# Mixers.net
KiCad netlist of a schematic drawn in Altium Designer
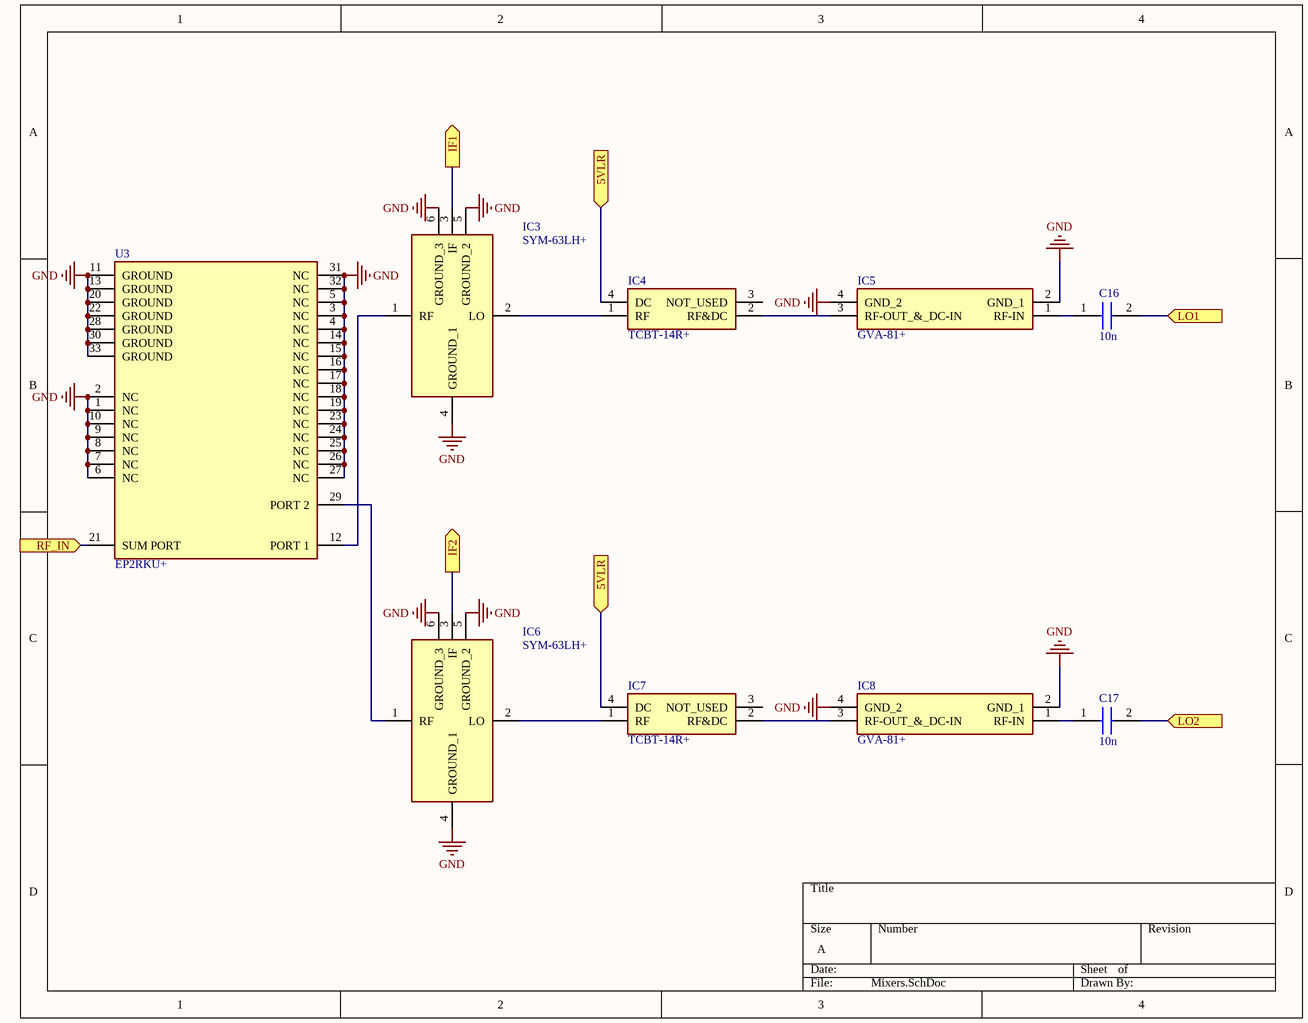
[diagram p0: Mixers.SchDoc]

(export (version "E")
  (design (tool "Eeschema 10.0.6"))
  (components
    (comp (ref "C16")
      (value "10n")
      (footprint "SamacSys:CAPC1005X61N")
      (description "Capacitor")
      (fields
        (field (name "MANUFACTURER_PART_NUMBER") "520L103KT16T")
        (field (name "MOUSER PART NUMBER") "581-520L103KT16T")
      )
      (libsource (lib "*") (part "520L103KT16T"))
    )
    (comp (ref "C17")
      (value "10n")
      (footprint "SamacSys:CAPC1005X61N")
      (description "Capacitor")
      (fields
        (field (name "MANUFACTURER_PART_NUMBER") "520L103KT16T")
        (field (name "MOUSER PART NUMBER") "581-520L103KT16T")
      )
      (libsource (lib "*") (part "520L103KT16T"))
    )
    (comp (ref "IC3")
      (value "SYM-63LH+")
      (footprint "SamacSys:SYM63LH")
      (description "Integrated Circuit")
      (fields (field (name "MOUSER PART NUMBER") "139-SYM-63LH"))
      (libsource (lib "*") (part "SYM-63LH+"))
    )
    (comp (ref "IC4")
      (value "TCBT-14R+")
      (footprint "SamacSys:TCBT14R")
      (description "Integrated Circuit")
      (fields (field (name "MOUSER PART NUMBER") "139-TCBT-14R"))
      (libsource (lib "*") (part "TCBT-14R+"))
    )
    (comp (ref "IC5")
      (value "GVA-81+")
      (footprint "SamacSys:GVA63")
      (description "Integrated Circuit")
      (fields (field (name "MOUSER PART NUMBER") "139-GVA-81"))
      (libsource (lib "*") (part "GVA-81+"))
    )
    (comp (ref "IC6")
      (value "SYM-63LH+")
      (footprint "SamacSys:SYM63LH")
      (description "Integrated Circuit")
      (fields (field (name "MOUSER PART NUMBER") "139-SYM-63LH"))
      (libsource (lib "*") (part "SYM-63LH+"))
    )
    (comp (ref "IC7")
      (value "TCBT-14R+")
      (footprint "SamacSys:TCBT14R")
      (description "Integrated Circuit")
      (fields (field (name "MOUSER PART NUMBER") "139-TCBT-14R"))
      (libsource (lib "*") (part "TCBT-14R+"))
    )
    (comp (ref "IC8")
      (value "GVA-81+")
      (footprint "SamacSys:GVA63")
      (description "Integrated Circuit")
      (fields (field (name "MOUSER PART NUMBER") "139-GVA-81"))
      (libsource (lib "*") (part "GVA-81+"))
    )
    (comp (ref "U3")
      (value "EP2RKU+")
      (footprint "FP-EP2RKU+-MFG")
      (description "EP2RKU+ 2 Ways MMIC Power Splitter, DC - 18000 MHz, 50Ω")
      (libsource (lib "Altium Content Vault") (part "6555140c254d169d6162399919444ec"))
    )
  )
  (nets
    (net (code "1") (name "/5VLR") (class "Default")
      (node (ref "IC4") (pin "4") (pinfunction "DC_4") (pintype "passive"))
      (node (ref "IC7") (pin "4") (pinfunction "DC_4") (pintype "passive"))
    )
    (net (code "2") (name "/IF1") (class "Default")
      (node (ref "IC3") (pin "3") (pinfunction "IF_3") (pintype "passive"))
    )
    (net (code "3") (name "/IF2") (class "Default")
      (node (ref "IC6") (pin "3") (pinfunction "IF_3") (pintype "passive"))
    )
    (net (code "4") (name "/LO1") (class "Default")
      (node (ref "C16") (pin "2") (pinfunction "2_2") (pintype "passive"))
    )
    (net (code "5") (name "/LO2") (class "Default")
      (node (ref "C17") (pin "2") (pinfunction "2_2") (pintype "passive"))
    )
    (net (code "6") (name "/RF_IN") (class "Default")
      (node (ref "U3") (pin "21") (pinfunction "SUM_PORT_21") (pintype "passive"))
    )
    (net (code "7") (name "GND") (class "Default")
      (node (ref "IC3") (pin "4") (pinfunction "GROUND_1_4") (pintype "passive"))
      (node (ref "IC3") (pin "5") (pinfunction "GROUND_2_5") (pintype "passive"))
      (node (ref "IC3") (pin "6") (pinfunction "GROUND_3_6") (pintype "passive"))
      (node (ref "IC5") (pin "2") (pinfunction "GND_1_2") (pintype "passive"))
      (node (ref "IC5") (pin "4") (pinfunction "GND_2_4") (pintype "passive"))
      (node (ref "IC6") (pin "4") (pinfunction "GROUND_1_4") (pintype "passive"))
      (node (ref "IC6") (pin "5") (pinfunction "GROUND_2_5") (pintype "passive"))
      (node (ref "IC6") (pin "6") (pinfunction "GROUND_3_6") (pintype "passive"))
      (node (ref "IC8") (pin "2") (pinfunction "GND_1_2") (pintype "passive"))
      (node (ref "IC8") (pin "4") (pinfunction "GND_2_4") (pintype "passive"))
      (node (ref "U3") (pin "1") (pinfunction "NC_1") (pintype "passive"))
      (node (ref "U3") (pin "10") (pinfunction "NC_10") (pintype "passive"))
      (node (ref "U3") (pin "11") (pinfunction "GROUND_11") (pintype "power_in"))
      (node (ref "U3") (pin "13") (pinfunction "GROUND_13") (pintype "power_in"))
      (node (ref "U3") (pin "14") (pinfunction "NC_14") (pintype "passive"))
      (node (ref "U3") (pin "15") (pinfunction "NC_15") (pintype "passive"))
      (node (ref "U3") (pin "16") (pinfunction "NC_16") (pintype "passive"))
      (node (ref "U3") (pin "17") (pinfunction "NC_17") (pintype "passive"))
      (node (ref "U3") (pin "18") (pinfunction "NC_18") (pintype "passive"))
      (node (ref "U3") (pin "19") (pinfunction "NC_19") (pintype "passive"))
      (node (ref "U3") (pin "2") (pinfunction "NC_2") (pintype "passive"))
      (node (ref "U3") (pin "20") (pinfunction "GROUND_20") (pintype "power_in"))
      (node (ref "U3") (pin "22") (pinfunction "GROUND_22") (pintype "power_in"))
      (node (ref "U3") (pin "23") (pinfunction "NC_23") (pintype "passive"))
      (node (ref "U3") (pin "24") (pinfunction "NC_24") (pintype "passive"))
      (node (ref "U3") (pin "25") (pinfunction "NC_25") (pintype "passive"))
      (node (ref "U3") (pin "26") (pinfunction "NC_26") (pintype "passive"))
      (node (ref "U3") (pin "27") (pinfunction "NC_27") (pintype "passive"))
      (node (ref "U3") (pin "28") (pinfunction "GROUND_28") (pintype "passive"))
      (node (ref "U3") (pin "3") (pinfunction "NC_3") (pintype "passive"))
      (node (ref "U3") (pin "30") (pinfunction "GROUND_30") (pintype "power_in"))
      (node (ref "U3") (pin "31") (pinfunction "NC_31") (pintype "passive"))
      (node (ref "U3") (pin "32") (pinfunction "NC_32") (pintype "passive"))
      (node (ref "U3") (pin "33") (pinfunction "GROUND_33") (pintype "power_in"))
      (node (ref "U3") (pin "4") (pinfunction "NC_4") (pintype "passive"))
      (node (ref "U3") (pin "5") (pinfunction "NC_5") (pintype "passive"))
      (node (ref "U3") (pin "6") (pinfunction "NC_6") (pintype "passive"))
      (node (ref "U3") (pin "7") (pinfunction "NC_7") (pintype "passive"))
      (node (ref "U3") (pin "8") (pinfunction "NC_8") (pintype "passive"))
      (node (ref "U3") (pin "9") (pinfunction "NC_9") (pintype "passive"))
    )
    (net (code "8") (name "Net-(IC3-LO)") (class "Default")
      (node (ref "IC3") (pin "2") (pinfunction "LO_2") (pintype "passive"))
      (node (ref "IC4") (pin "1") (pinfunction "RF_1") (pintype "passive"))
    )
    (net (code "9") (name "Net-(IC3-RF)") (class "Default")
      (node (ref "IC3") (pin "1") (pinfunction "RF_1") (pintype "passive"))
      (node (ref "U3") (pin "12") (pinfunction "PORT_1_12") (pintype "passive"))
    )
    (net (code "10") (name "Net-(IC4-RF&DC)") (class "Default")
      (node (ref "IC4") (pin "2") (pinfunction "RF&DC_2") (pintype "passive"))
      (node (ref "IC5") (pin "3") (pinfunction "RF-OUT_&_DC-IN_3") (pintype "passive"))
    )
    (net (code "11") (name "Net-(IC5-RF-IN)") (class "Default")
      (node (ref "C16") (pin "1") (pinfunction "1_1") (pintype "passive"))
      (node (ref "IC5") (pin "1") (pinfunction "RF-IN_1") (pintype "passive"))
    )
    (net (code "12") (name "Net-(IC6-LO)") (class "Default")
      (node (ref "IC6") (pin "2") (pinfunction "LO_2") (pintype "passive"))
      (node (ref "IC7") (pin "1") (pinfunction "RF_1") (pintype "passive"))
    )
    (net (code "13") (name "Net-(IC6-RF)") (class "Default")
      (node (ref "IC6") (pin "1") (pinfunction "RF_1") (pintype "passive"))
      (node (ref "U3") (pin "29") (pinfunction "PORT_2_29") (pintype "passive"))
    )
    (net (code "14") (name "Net-(IC7-RF&DC)") (class "Default")
      (node (ref "IC7") (pin "2") (pinfunction "RF&DC_2") (pintype "passive"))
      (node (ref "IC8") (pin "3") (pinfunction "RF-OUT_&_DC-IN_3") (pintype "passive"))
    )
    (net (code "15") (name "Net-(IC8-RF-IN)") (class "Default")
      (node (ref "C17") (pin "1") (pinfunction "1_1") (pintype "passive"))
      (node (ref "IC8") (pin "1") (pinfunction "RF-IN_1") (pintype "passive"))
    )
    (net (code "16") (name "unconnected-(IC4-NOT_USED-Pad3)") (class "Default")
      (node (ref "IC4") (pin "3") (pinfunction "NOT_USED_3") (pintype "passive"))
    )
    (net (code "17") (name "unconnected-(IC7-NOT_USED-Pad3)") (class "Default")
      (node (ref "IC7") (pin "3") (pinfunction "NOT_USED_3") (pintype "passive"))
    )
  )
)
